# RFM12DipAdapter.net
KiCad netlist of a schematic drawn in EAGLE
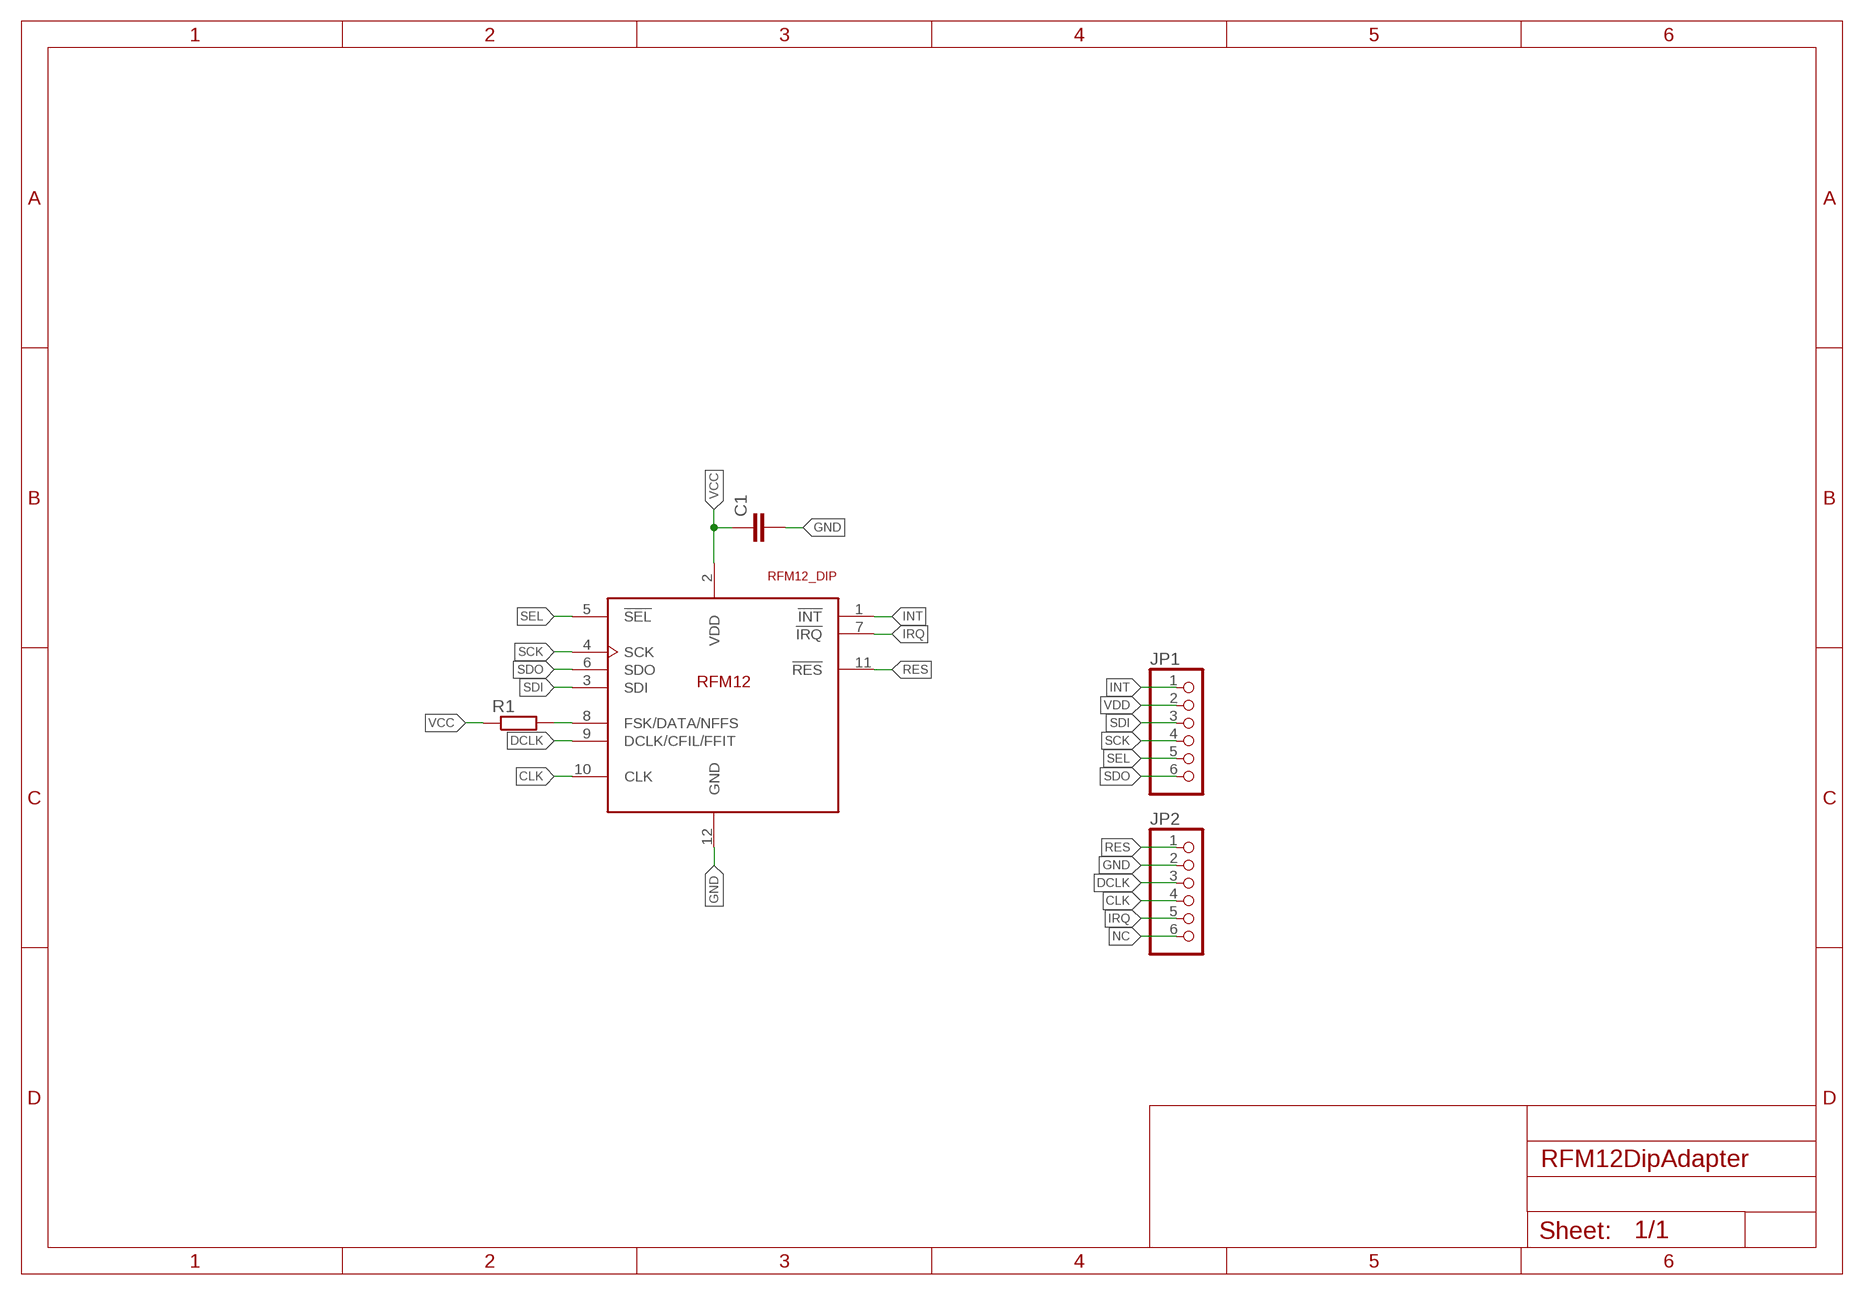
[diagram p0: schematic, sheet 1]

(export (version "E")
  (design (tool "Eeschema 10.0.6"))
  (components
    (comp (ref "C1")
      (value "C-EUC0805")
      (footprint "eagle-import:C0805")
      (libsource (lib "eagle-import") (part "C-EUC0805"))
    )
    (comp (ref "JP1")
      (value "PINHD-1X6")
      (footprint "eagle-import:1X06")
      (libsource (lib "eagle-import") (part "PINHD-1X6"))
    )
    (comp (ref "JP2")
      (value "PINHD-1X6")
      (footprint "eagle-import:1X06")
      (libsource (lib "eagle-import") (part "PINHD-1X6"))
    )
    (comp (ref "R1")
      (value "R-EU_R1206")
      (footprint "eagle-import:R1206")
      (libsource (lib "eagle-import") (part "R-EU_R1206"))
    )
    (comp (ref "U$1")
      (value "RFM12_DIP")
      (footprint "eagle-import:DIL-2MM-2X06")
      (libsource (lib "eagle-import") (part "RFM12_DIP"))
    )
  )
  (nets
    (net (code "1") (name "CLK") (class "Default")
      (node (ref "JP2") (pin "4") (pinfunction "4_4") (pintype "passive"))
      (node (ref "U$1") (pin "10") (pinfunction "CLK_10") (pintype "output"))
    )
    (net (code "2") (name "DCLK") (class "Default")
      (node (ref "JP2") (pin "3") (pinfunction "3_3") (pintype "passive"))
      (node (ref "U$1") (pin "9") (pinfunction "DCLK/CFIL/FFIT_9") (pintype "bidirectional"))
    )
    (net (code "3") (name "GND") (class "Default")
      (node (ref "C1") (pin "2") (pinfunction "2_2") (pintype "passive"))
      (node (ref "JP2") (pin "2") (pinfunction "2_2") (pintype "passive"))
      (node (ref "U$1") (pin "12") (pinfunction "GND_12") (pintype "passive"))
    )
    (net (code "4") (name "INT") (class "Default")
      (node (ref "JP1") (pin "1") (pinfunction "1_1") (pintype "passive"))
      (node (ref "U$1") (pin "1") (pinfunction "~{INT}_1") (pintype "bidirectional"))
    )
    (net (code "5") (name "IRQ") (class "Default")
      (node (ref "JP2") (pin "5") (pinfunction "5_5") (pintype "passive"))
      (node (ref "U$1") (pin "7") (pinfunction "~{IRQ}_7") (pintype "output"))
    )
    (net (code "6") (name "NC") (class "Default")
      (node (ref "JP2") (pin "6") (pinfunction "6_6") (pintype "passive"))
    )
    (net (code "7") (name "Net-(U$1-FSK{slash}DATA{slash}NFFS)") (class "Default")
      (node (ref "R1") (pin "2") (pinfunction "2_2") (pintype "passive"))
      (node (ref "U$1") (pin "8") (pinfunction "FSK/DATA/NFFS_8") (pintype "bidirectional"))
    )
    (net (code "8") (name "RES") (class "Default")
      (node (ref "JP2") (pin "1") (pinfunction "1_1") (pintype "passive"))
      (node (ref "U$1") (pin "11") (pinfunction "~{RES}_11") (pintype "bidirectional"))
    )
    (net (code "9") (name "SCK") (class "Default")
      (node (ref "JP1") (pin "4") (pinfunction "4_4") (pintype "passive"))
      (node (ref "U$1") (pin "4") (pinfunction "SCK_4") (pintype "input"))
    )
    (net (code "10") (name "SDI") (class "Default")
      (node (ref "JP1") (pin "3") (pinfunction "3_3") (pintype "passive"))
      (node (ref "U$1") (pin "3") (pinfunction "SDI_3") (pintype "input"))
    )
    (net (code "11") (name "SDO") (class "Default")
      (node (ref "JP1") (pin "6") (pinfunction "6_6") (pintype "passive"))
      (node (ref "U$1") (pin "6") (pinfunction "SDO_6") (pintype "output"))
    )
    (net (code "12") (name "SEL") (class "Default")
      (node (ref "JP1") (pin "5") (pinfunction "5_5") (pintype "passive"))
      (node (ref "U$1") (pin "5") (pinfunction "~{SEL}_5") (pintype "input"))
    )
    (net (code "13") (name "VCC") (class "Default")
      (node (ref "C1") (pin "1") (pinfunction "1_1") (pintype "passive"))
      (node (ref "R1") (pin "1") (pinfunction "1_1") (pintype "passive"))
      (node (ref "U$1") (pin "2") (pinfunction "VDD_2") (pintype "power_in"))
    )
    (net (code "14") (name "VDD") (class "Default")
      (node (ref "JP1") (pin "2") (pinfunction "2_2") (pintype "passive"))
    )
  )
)
